# qr_reader.net
KiCad netlist of a schematic drawn in Altium Designer
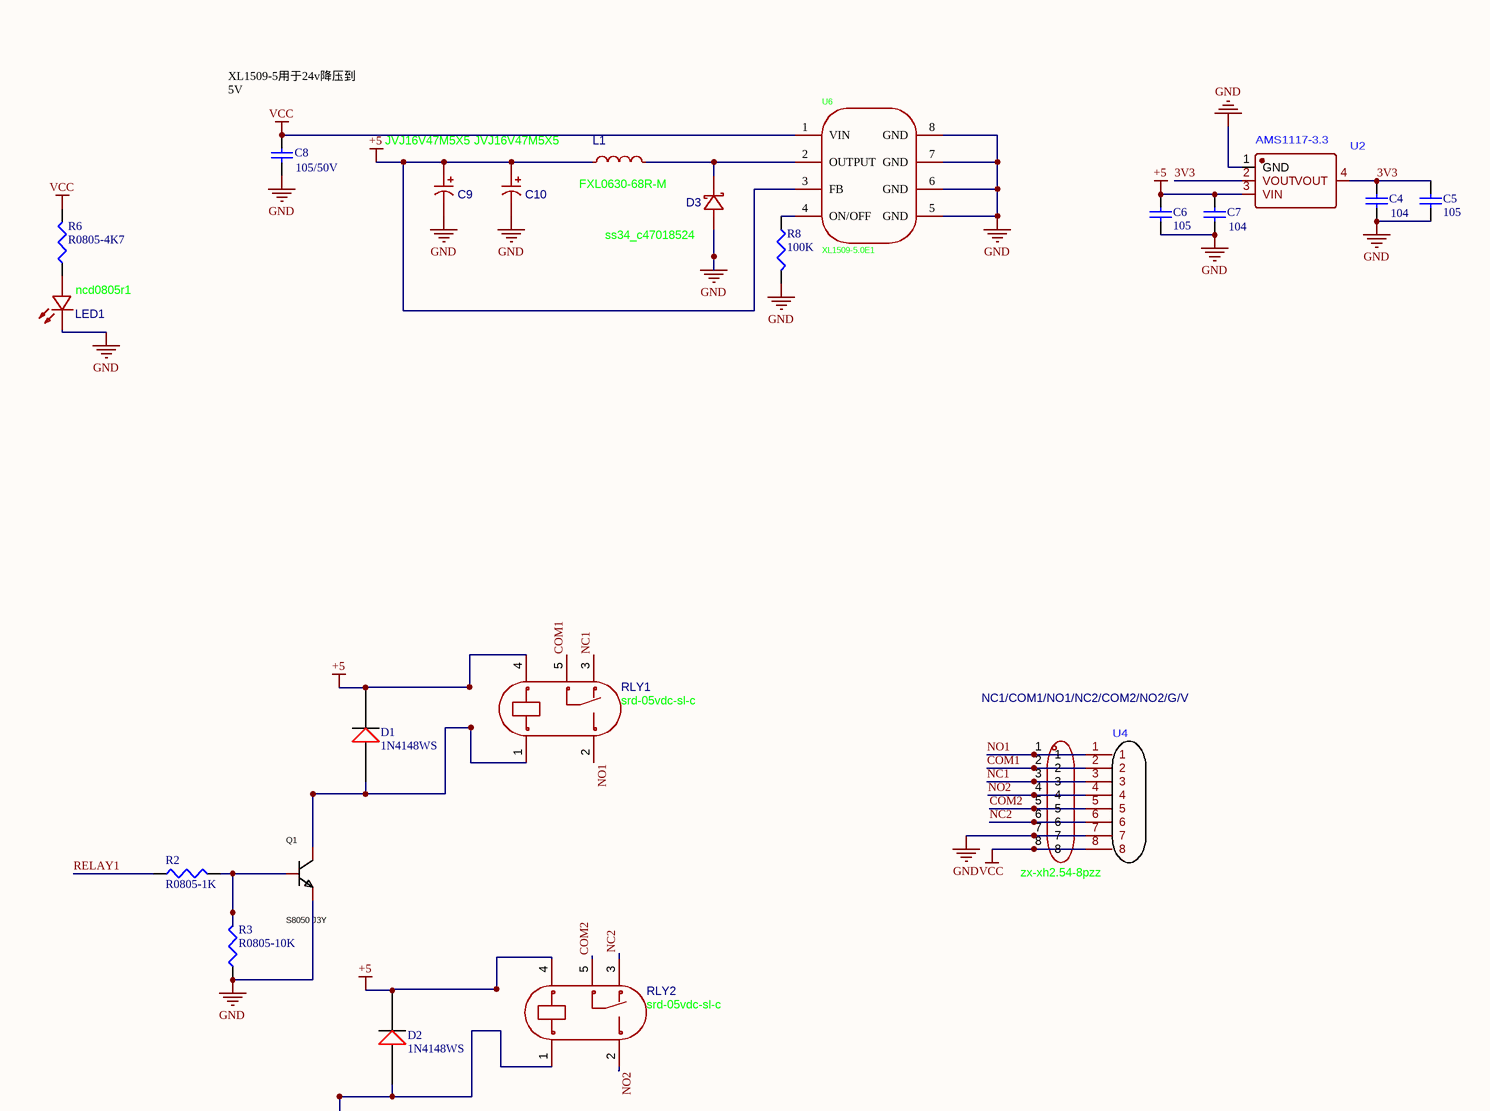
[diagram p0: qr reader.SchDoc, top left]
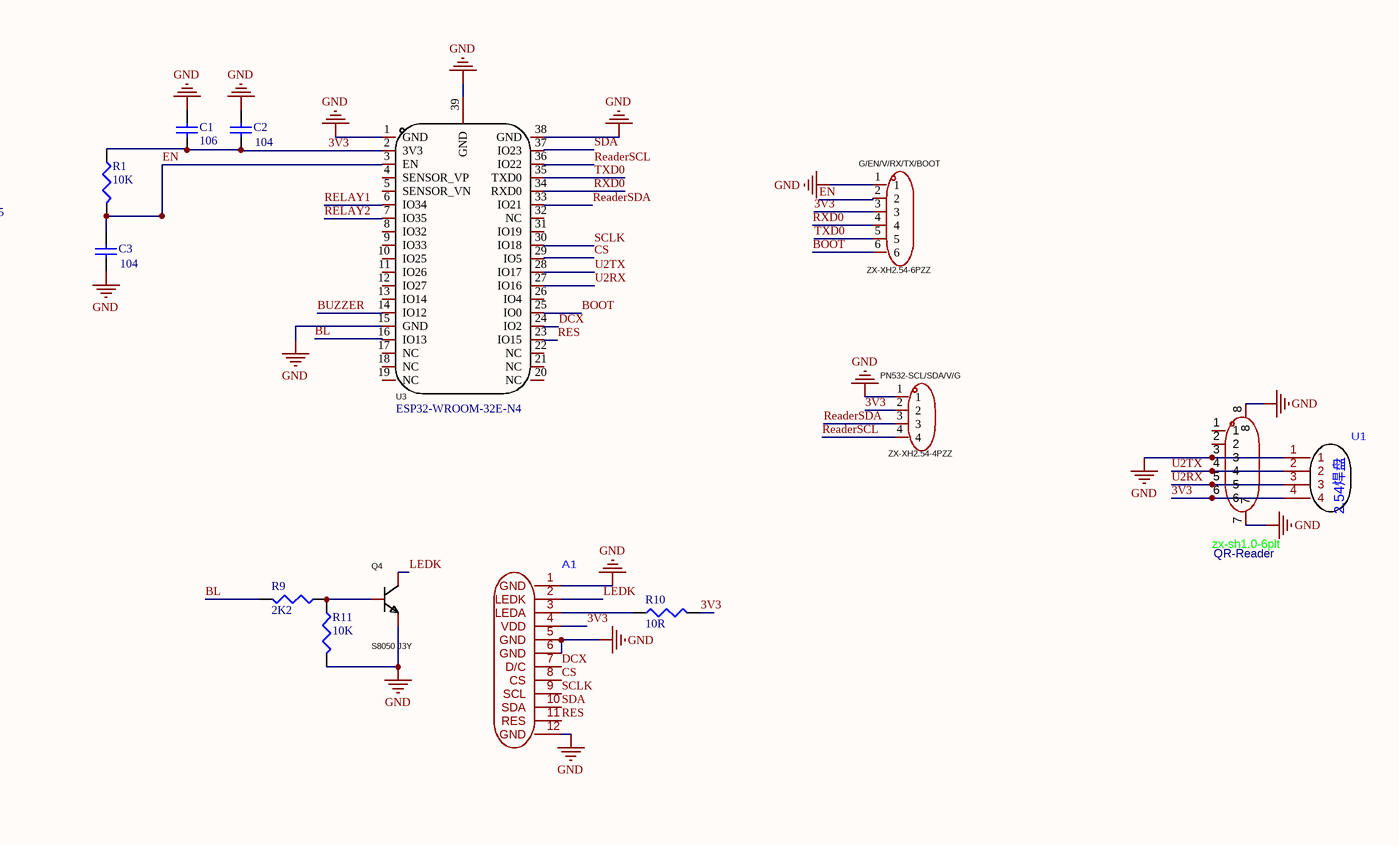
[diagram p1: qr reader.SchDoc, top right]
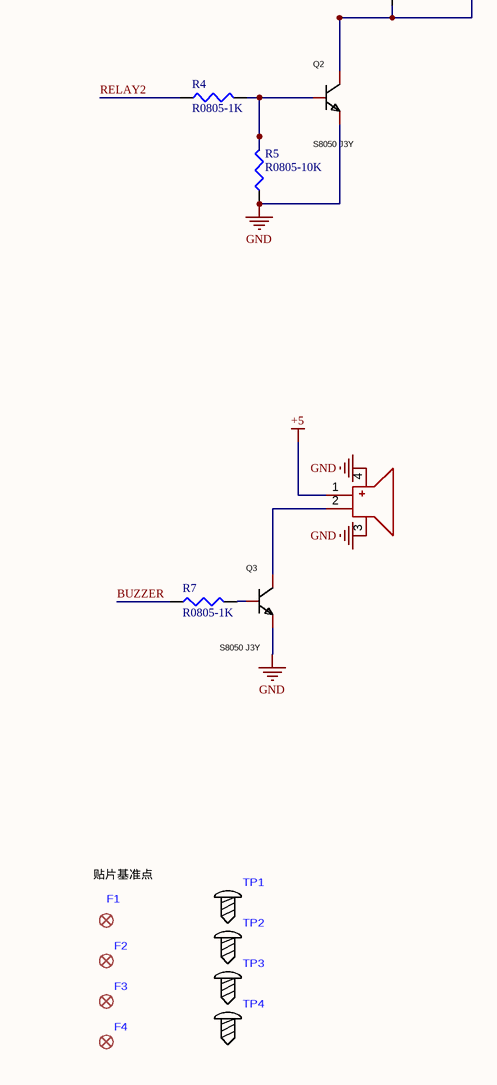
[diagram p2: qr reader.SchDoc, bottom left]

(export (version "E")
  (design (tool "Eeschema 10.0.6"))
  (components
    (comp (ref "A1")
      (value "~")
      (footprint "tft SCREEN")
      (libsource (lib "altium-import") (part "root_0_TFT1.54_"))
    )
    (comp (ref "BUZZER1")
      (value "klj-8530-5027")
      (footprint "BUZ-SMD_4P-L8.5-W8.5-TL")
      (fields (field (name "MANUFACTURER") "KELIKING(凯丽金)") (field (name "MANUFACTURERPART") "KLJ-8530-5027"))
      (libsource (lib "altium-import") (part "root_0_klj-8530-5027_"))
    )
    (comp (ref "C1")
      (value "106")
      (footprint "0805")
      (description "Capacitor (Semiconductor SIM Model)")
      (fields (field (name "Comment") "Cap Semi") (field (name "PUBLISHER") "Altium Limited"))
      (libsource (lib "Schlib1") (part "Cap Semi"))
    )
    (comp (ref "C2")
      (value "104")
      (footprint "0805")
      (description "Capacitor (Semiconductor SIM Model)")
      (fields (field (name "Comment") "Cap Semi") (field (name "PUBLISHER") "Altium Limited"))
      (libsource (lib "Schlib1") (part "Cap Semi"))
    )
    (comp (ref "C3")
      (value "104")
      (footprint "0805")
      (description "Capacitor (Semiconductor SIM Model)")
      (fields (field (name "Comment") "Cap Semi") (field (name "PUBLISHER") "Altium Limited"))
      (libsource (lib "Schlib1") (part "Cap Semi"))
    )
    (comp (ref "C4")
      (value "104")
      (footprint "0805")
      (description "Capacitor (Semiconductor SIM Model)")
      (fields (field (name "Comment") "Cap Semi") (field (name "PUBLISHER") "Altium Limited"))
      (libsource (lib "Schlib1") (part "Cap Semi"))
    )
    (comp (ref "C5")
      (value "105")
      (footprint "0805")
      (description "Capacitor (Semiconductor SIM Model)")
      (fields (field (name "Comment") "Cap Semi") (field (name "PUBLISHER") "Altium Limited"))
      (libsource (lib "Schlib1") (part "Cap Semi"))
    )
    (comp (ref "C6")
      (value "105")
      (footprint "0805")
      (description "Capacitor (Semiconductor SIM Model)")
      (fields (field (name "Comment") "Cap Semi") (field (name "PUBLISHER") "Altium Limited"))
      (libsource (lib "Schlib1") (part "Cap Semi"))
    )
    (comp (ref "C7")
      (value "104")
      (footprint "0805")
      (description "Capacitor (Semiconductor SIM Model)")
      (fields (field (name "Comment") "Cap Semi") (field (name "PUBLISHER") "Altium Limited"))
      (libsource (lib "Schlib1") (part "Cap Semi"))
    )
    (comp (ref "C8")
      (value "105/50V")
      (footprint "0805")
      (description "Capacitor (Semiconductor SIM Model)")
      (fields (field (name "Comment") "105") (field (name "PUBLISHER") "Altium Limited"))
      (libsource (lib "Schlib1") (part "Cap Semi"))
    )
    (comp (ref "C9")
      (value "JVJ16V47M5X5")
      (footprint "CAP-SMD_BD5.0-L5.3-W5.3-LS6.5-FD-1")
      (libsource (lib "altium-import") (part "root_3_JVJ16V47M5X5_"))
    )
    (comp (ref "C10")
      (value "JVJ16V47M5X5")
      (footprint "CAP-SMD_BD5.0-L5.3-W5.3-LS6.5-FD-1")
      (libsource (lib "altium-import") (part "root_3_JVJ16V47M5X5_"))
    )
    (comp (ref "D1") (value "1N4148WS") (footprint "SOD323") (libsource (lib "Schlib1") (part "1N4148WS")))
    (comp (ref "D2") (value "1N4148WS") (footprint "SOD323") (libsource (lib "Schlib1") (part "1N4148WS")))
    (comp (ref "D3")
      (value "ss34_c47018524")
      (footprint "SMA_L4.3-W2.6-LS5.0-RD")
      (description "二极管配置:独立式;直流反向耐压(Vr):40V;整流电流:3A;")
      (fields (field (name "MANUFACTURER") "baocheng(宝乘)") (field (name "MANUFACTURERPART") "SS34"))
      (libsource (lib "altium-import") (part "root_3_ss34_c47018524_"))
    )
    (comp (ref "F1")
      (value "~")
      (footprint "FIDUCIAL-1.5X3")
      (libsource (lib "altium-import") (part "root_0_FIDUCIAL1.5X3_"))
    )
    (comp (ref "F2")
      (value "~")
      (footprint "FIDUCIAL-1.5X3")
      (libsource (lib "altium-import") (part "root_0_FIDUCIAL1.5X3_"))
    )
    (comp (ref "F3")
      (value "~")
      (footprint "FIDUCIAL-1.5X3")
      (libsource (lib "altium-import") (part "root_0_FIDUCIAL1.5X3_"))
    )
    (comp (ref "F4")
      (value "~")
      (footprint "FIDUCIAL-1.5X3")
      (libsource (lib "altium-import") (part "root_0_FIDUCIAL1.5X3_"))
    )
    (comp (ref "G/EN/V/RX/TX/BOOT")
      (value "ZX-XH2.54-6PZZ")
      (footprint "CONN-TH_6P-P2.50_ZX-XH2.54-6PZZ")
      (fields (field (name "MANUFACTURER") "Megastar(兆星)"))
      (libsource (lib "altium-import") (part "root_0_ZX-XH2.54-6PZZ_"))
    )
    (comp (ref "L1")
      (value "FXL0630-68R-M")
      (footprint "0630 - duplicate")
      (libsource (lib "altium-import") (part "root_0_FXL0630-8R2-M_"))
    )
    (comp (ref "LED1")
      (value "ncd0805r1")
      (footprint "LED0805-RD")
      (fields (field (name "MANUFACTURER") "国星光电") (field (name "MANUFACTURERPART") "NCD0805R1"))
      (libsource (lib "altium-import") (part "root_1_ncd0805r1_"))
    )
    (comp (ref "NC1/COM1/NO1/NC2/COM2/NO2/G/V")
      (value "zx-xh2.54-8pzz")
      (footprint "CONN-TH_8P-P2.50-XH2.54-8P")
      (fields (field (name "MANUFACTURER") "Megastar(兆星)") (field (name "MANUFACTURERPART") "ZX-XH2.54-8PZZ"))
      (libsource (lib "altium-import") (part "root_0_zx-xh2.54-8pzz_"))
    )
    (comp (ref "PN532-SCL/SDA/V/G")
      (value "ZX-XH2.54-4PZZ")
      (footprint "CONN-TH_4P-P2.50_4PIN")
      (fields (field (name "MANUFACTURER") "Megastar(兆星)"))
      (libsource (lib "altium-import") (part "root_0_ZX-XH2.54-4PZZ_"))
    )
    (comp (ref "Q1")
      (value "S8050 J3Y")
      (footprint "SOT-23-3_L3.0-W1.7-P0.95-LS2.9-BR")
      (fields (field (name "MANUFACTURER") "CJ(江苏长电/长晶)"))
      (libsource (lib "altium-import") (part "root_0_S8050 J3Y_C2146_"))
    )
    (comp (ref "Q2")
      (value "S8050 J3Y")
      (footprint "SOT-23-3_L3.0-W1.7-P0.95-LS2.9-BR")
      (fields (field (name "MANUFACTURER") "CJ(江苏长电/长晶)"))
      (libsource (lib "altium-import") (part "root_0_S8050 J3Y_C2146_"))
    )
    (comp (ref "Q3")
      (value "S8050 J3Y")
      (footprint "SOT-23-3_L3.0-W1.7-P0.95-LS2.9-BR")
      (fields (field (name "MANUFACTURER") "CJ(江苏长电/长晶)"))
      (libsource (lib "altium-import") (part "root_0_S8050 J3Y_C2146_"))
    )
    (comp (ref "Q4")
      (value "S8050 J3Y")
      (footprint "SOT-23-3_L3.0-W1.7-P0.95-LS2.9-BR")
      (fields (field (name "MANUFACTURER") "CJ(江苏长电/长晶)"))
      (libsource (lib "altium-import") (part "root_0_S8050 J3Y_C2146_"))
    )
    (comp (ref "QR-Reader")
      (value "zx-sh1.0-6plt")
      (footprint "CONN-SMD_6P-P1.00_ZX-SH1.0-6PLT")
      (fields (field (name "MANUFACTURER") "Megastar(兆星)") (field (name "MANUFACTURERPART") "ZX-SH1.0-6PLT"))
      (libsource (lib "altium-import") (part "root_0_zx-sh1.0-6plt_"))
    )
    (comp (ref "R1")
      (value "10K")
      (footprint "0805")
      (description "Resistor")
      (fields (field (name "Comment") "Res3") (field (name "PUBLISHER") "Altium Limited"))
      (libsource (lib "Schlib1") (part "Res3"))
    )
    (comp (ref "R2")
      (value "R0805-1K")
      (footprint "0805")
      (description "Resistor")
      (fields (field (name "PUBLISHER") "Altium Limited"))
      (libsource (lib "Schlib1") (part "Res3"))
    )
    (comp (ref "R3")
      (value "R0805-10K")
      (footprint "0805")
      (description "Resistor")
      (fields (field (name "PUBLISHER") "Altium Limited"))
      (libsource (lib "Schlib1") (part "Res3"))
    )
    (comp (ref "R4")
      (value "R0805-1K")
      (footprint "0805")
      (description "Resistor")
      (fields (field (name "PUBLISHER") "Altium Limited"))
      (libsource (lib "Schlib1") (part "Res3"))
    )
    (comp (ref "R5")
      (value "R0805-10K")
      (footprint "0805")
      (description "Resistor")
      (fields (field (name "PUBLISHER") "Altium Limited"))
      (libsource (lib "Schlib1") (part "Res3"))
    )
    (comp (ref "R6")
      (value "R0805-4K7")
      (footprint "0805")
      (description "Resistor")
      (fields (field (name "PUBLISHER") "Altium Limited"))
      (libsource (lib "Schlib1") (part "Res3"))
    )
    (comp (ref "R7")
      (value "R0805-1K")
      (footprint "0805")
      (description "Resistor")
      (fields (field (name "PUBLISHER") "Altium Limited"))
      (libsource (lib "Schlib1") (part "Res3"))
    )
    (comp (ref "R8")
      (value "100K")
      (footprint "0805")
      (description "Resistor")
      (fields (field (name "PUBLISHER") "Altium Limited"))
      (libsource (lib "Schlib1") (part "Res3"))
    )
    (comp (ref "R9")
      (value "2K2")
      (footprint "0805")
      (description "Resistor")
      (fields (field (name "Comment") "Res3") (field (name "PUBLISHER") "Altium Limited"))
      (libsource (lib "Schlib1") (part "Res3"))
    )
    (comp (ref "R10")
      (value "10R")
      (footprint "0805")
      (description "Resistor")
      (fields (field (name "Comment") "Res3") (field (name "PUBLISHER") "Altium Limited"))
      (libsource (lib "Schlib1") (part "Res3"))
    )
    (comp (ref "R11")
      (value "10K")
      (footprint "0805")
      (description "Resistor")
      (fields (field (name "Comment") "Res3") (field (name "PUBLISHER") "Altium Limited"))
      (libsource (lib "Schlib1") (part "Res3"))
    )
    (comp (ref "RLY1")
      (value "srd-05vdc-sl-c")
      (footprint "RELAY-TH_SRD-XXVDC-XL-C")
      (description "线圈电压:5V;触点形式:一组转换:1C(单刀双掷-转换);触点容量(电阻负载):-;最大切换电压:250V@AC;最大切换电流:15A;")
      (fields (field (name "MANUFACTURER") "松乐") (field (name "MANUFACTURERPART") "SRD-05VDC-SL-C"))
      (libsource (lib "altium-import") (part "root_3_srd-05vdc-sl-c_"))
    )
    (comp (ref "RLY2")
      (value "srd-05vdc-sl-c")
      (footprint "RELAY-TH_SRD-XXVDC-XL-C")
      (description "线圈电压:5V;触点形式:一组转换:1C(单刀双掷-转换);触点容量(电阻负载):-;最大切换电压:250V@AC;最大切换电流:15A;")
      (fields (field (name "MANUFACTURER") "松乐") (field (name "MANUFACTURERPART") "SRD-05VDC-SL-C"))
      (libsource (lib "altium-import") (part "root_3_srd-05vdc-sl-c_"))
    )
    (comp (ref "TP1")
      (value "~")
      (footprint "PCBComponent_1 - duplicate")
      (libsource (lib "altium-import") (part "root_0_M3铜柱_"))
    )
    (comp (ref "TP2")
      (value "~")
      (footprint "PCBComponent_1 - duplicate")
      (libsource (lib "altium-import") (part "root_0_M3铜柱_"))
    )
    (comp (ref "TP3")
      (value "~")
      (footprint "PCBComponent_1 - duplicate")
      (libsource (lib "altium-import") (part "root_0_M3铜柱_"))
    )
    (comp (ref "TP4")
      (value "~")
      (footprint "PCBComponent_1 - duplicate")
      (libsource (lib "altium-import") (part "root_0_M3铜柱_"))
    )
    (comp (ref "U1")
      (value "~")
      (footprint "2.54_PAD_4P")
      (libsource (lib "altium-import") (part "root_0_当面2.54焊盘_"))
    )
    (comp (ref "U2")
      (value "AMS1117-3.3")
      (footprint "SOT-223-3_L6.7-W3.7-P2.30-LS7.0-BR")
      (libsource (lib "altium-import") (part "root_0_AMS1117-3.3_C917183_"))
    )
    (comp (ref "U3")
      (value "ESP32-WROOM-32E-N4")
      (footprint "WIFI-SMD_ESP32-WROOM-32E")
      (fields (field (name "MANUFACTURER") "ESPRESSIF(乐鑫)"))
      (libsource (lib "altium-import") (part "root_0_ESP32-WROOM-32E-N4_"))
    )
    (comp (ref "U4")
      (value "~")
      (footprint "3.96_PAD_8P")
      (libsource (lib "altium-import") (part "root_2_8P焊盘底面层_"))
    )
    (comp (ref "U6")
      (value "XL1509-5.0E1")
      (footprint "SOIC-8_L5.0-W4.0-P1.27-LS6.0-BL")
      (fields (field (name "MANUFACTURER") "XLSEMI(芯龙)"))
      (libsource (lib "altium-import") (part "root_0_XL1509-5.0E1_"))
    )
  )
  (nets
    (net (code "1") (name "+5") (class "Default")
      (node (ref "BUZZER1") (pin "1") (pinfunction "+_1") (pintype "passive"))
      (node (ref "C10") (pin "1") (pinfunction "1_1") (pintype "passive"))
      (node (ref "C6") (pin "1") (pinfunction "1_1") (pintype "passive"))
      (node (ref "C7") (pin "2") (pinfunction "2_2") (pintype "passive"))
      (node (ref "C9") (pin "1") (pinfunction "1_1") (pintype "passive"))
      (node (ref "D1") (pin "2") (pinfunction "2_2") (pintype "passive"))
      (node (ref "D2") (pin "2") (pinfunction "2_2") (pintype "passive"))
      (node (ref "L1") (pin "1") (pinfunction "1_1") (pintype "passive"))
      (node (ref "RLY1") (pin "4") (pinfunction "4_4") (pintype "passive"))
      (node (ref "RLY2") (pin "4") (pinfunction "4_4") (pintype "passive"))
      (node (ref "U2") (pin "3") (pinfunction "VIN_3") (pintype "passive"))
      (node (ref "U6") (pin "3") (pinfunction "FB_3") (pintype "passive"))
    )
    (net (code "2") (name "/3V3") (class "Default")
      (node (ref "A1") (pin "4") (pinfunction "VDD_4") (pintype "passive"))
      (node (ref "C1") (pin "2") (pinfunction "2_2") (pintype "passive"))
      (node (ref "C2") (pin "1") (pinfunction "1_1") (pintype "passive"))
      (node (ref "C4") (pin "2") (pinfunction "2_2") (pintype "passive"))
      (node (ref "C5") (pin "1") (pinfunction "1_1") (pintype "passive"))
      (node (ref "G/EN/V/RX/TX/BOOT") (pin "3") (pinfunction "3_3") (pintype "passive"))
      (node (ref "PN532-SCL/SDA/V/G") (pin "2") (pinfunction "2_2") (pintype "passive"))
      (node (ref "QR-Reader") (pin "6") (pinfunction "6_6") (pintype "passive"))
      (node (ref "R1") (pin "1") (pinfunction "1_1") (pintype "passive"))
      (node (ref "R10") (pin "2") (pinfunction "2_2") (pintype "passive"))
      (node (ref "U1") (pin "4") (pinfunction "4_4") (pintype "passive"))
      (node (ref "U2") (pin "2") (pinfunction "VOUT_2") (pintype "passive"))
      (node (ref "U2") (pin "4") (pinfunction "VOUT_4") (pintype "passive"))
      (node (ref "U3") (pin "2") (pinfunction "3V3_2") (pintype "passive"))
    )
    (net (code "3") (name "/BL") (class "Default")
      (node (ref "R9") (pin "2") (pinfunction "2_2") (pintype "passive"))
      (node (ref "U3") (pin "16") (pinfunction "IO13_16") (pintype "passive"))
    )
    (net (code "4") (name "/BOOT") (class "Default")
      (node (ref "G/EN/V/RX/TX/BOOT") (pin "6") (pinfunction "6_6") (pintype "passive"))
      (node (ref "U3") (pin "25") (pinfunction "IO0_25") (pintype "passive"))
    )
    (net (code "5") (name "/BUZZER") (class "Default")
      (node (ref "R7") (pin "1") (pinfunction "1_1") (pintype "passive"))
      (node (ref "U3") (pin "14") (pinfunction "IO12_14") (pintype "passive"))
    )
    (net (code "6") (name "/COM1") (class "Default")
      (node (ref "NC1/COM1/NO1/NC2/COM2/NO2/G/V") (pin "2") (pinfunction "2_2") (pintype "passive"))
      (node (ref "RLY1") (pin "5") (pinfunction "5_5") (pintype "passive"))
      (node (ref "U4") (pin "2") (pinfunction "2_2") (pintype "passive"))
    )
    (net (code "7") (name "/COM2") (class "Default")
      (node (ref "NC1/COM1/NO1/NC2/COM2/NO2/G/V") (pin "5") (pinfunction "5_5") (pintype "passive"))
      (node (ref "RLY2") (pin "5") (pinfunction "5_5") (pintype "passive"))
      (node (ref "U4") (pin "5") (pinfunction "5_5") (pintype "passive"))
    )
    (net (code "8") (name "/CS") (class "Default")
      (node (ref "A1") (pin "8") (pinfunction "CS_8") (pintype "passive"))
      (node (ref "U3") (pin "29") (pinfunction "IO5_29") (pintype "passive"))
    )
    (net (code "9") (name "/DCX") (class "Default")
      (node (ref "A1") (pin "7") (pinfunction "D/C_7") (pintype "passive"))
      (node (ref "U3") (pin "24") (pinfunction "IO2_24") (pintype "passive"))
    )
    (net (code "10") (name "/EN") (class "Default")
      (node (ref "C3") (pin "2") (pinfunction "2_2") (pintype "passive"))
      (node (ref "G/EN/V/RX/TX/BOOT") (pin "2") (pinfunction "2_2") (pintype "passive"))
      (node (ref "R1") (pin "2") (pinfunction "2_2") (pintype "passive"))
      (node (ref "U3") (pin "3") (pinfunction "EN_3") (pintype "passive"))
    )
    (net (code "11") (name "/LEDK") (class "Default")
      (node (ref "A1") (pin "2") (pinfunction "LEDK_2") (pintype "passive"))
      (node (ref "Q4") (pin "3") (pinfunction "C_3") (pintype "passive"))
    )
    (net (code "12") (name "/NC1") (class "Default")
      (node (ref "NC1/COM1/NO1/NC2/COM2/NO2/G/V") (pin "3") (pinfunction "3_3") (pintype "passive"))
      (node (ref "RLY1") (pin "3") (pinfunction "3_3") (pintype "passive"))
      (node (ref "U4") (pin "3") (pinfunction "3_3") (pintype "passive"))
    )
    (net (code "13") (name "/NC2") (class "Default")
      (node (ref "NC1/COM1/NO1/NC2/COM2/NO2/G/V") (pin "6") (pinfunction "6_6") (pintype "passive"))
      (node (ref "RLY2") (pin "3") (pinfunction "3_3") (pintype "passive"))
      (node (ref "U4") (pin "6") (pinfunction "6_6") (pintype "passive"))
    )
    (net (code "14") (name "/NO1") (class "Default")
      (node (ref "NC1/COM1/NO1/NC2/COM2/NO2/G/V") (pin "1") (pinfunction "1_1") (pintype "passive"))
      (node (ref "RLY1") (pin "2") (pinfunction "2_2") (pintype "passive"))
      (node (ref "U4") (pin "1") (pinfunction "1_1") (pintype "passive"))
    )
    (net (code "15") (name "/NO2") (class "Default")
      (node (ref "NC1/COM1/NO1/NC2/COM2/NO2/G/V") (pin "4") (pinfunction "4_4") (pintype "passive"))
      (node (ref "RLY2") (pin "2") (pinfunction "2_2") (pintype "passive"))
      (node (ref "U4") (pin "4") (pinfunction "4_4") (pintype "passive"))
    )
    (net (code "16") (name "/RELAY1") (class "Default")
      (node (ref "R2") (pin "1") (pinfunction "1_1") (pintype "passive"))
      (node (ref "U3") (pin "6") (pinfunction "IO34_6") (pintype "passive"))
    )
    (net (code "17") (name "/RELAY2") (class "Default")
      (node (ref "R4") (pin "1") (pinfunction "1_1") (pintype "passive"))
      (node (ref "U3") (pin "7") (pinfunction "IO35_7") (pintype "passive"))
    )
    (net (code "18") (name "/RES") (class "Default")
      (node (ref "A1") (pin "11") (pinfunction "RES_11") (pintype "passive"))
      (node (ref "U3") (pin "23") (pinfunction "IO15_23") (pintype "passive"))
    )
    (net (code "19") (name "/RXD0") (class "Default")
      (node (ref "G/EN/V/RX/TX/BOOT") (pin "4") (pinfunction "4_4") (pintype "passive"))
      (node (ref "U3") (pin "34") (pinfunction "RXD0_34") (pintype "passive"))
    )
    (net (code "20") (name "/ReaderSCL") (class "Default")
      (node (ref "PN532-SCL/SDA/V/G") (pin "4") (pinfunction "4_4") (pintype "passive"))
      (node (ref "U3") (pin "36") (pinfunction "IO22_36") (pintype "passive"))
    )
    (net (code "21") (name "/ReaderSDA") (class "Default")
      (node (ref "PN532-SCL/SDA/V/G") (pin "3") (pinfunction "3_3") (pintype "passive"))
      (node (ref "U3") (pin "33") (pinfunction "IO21_33") (pintype "passive"))
    )
    (net (code "22") (name "/SCLK") (class "Default")
      (node (ref "A1") (pin "9") (pinfunction "SCL_9") (pintype "passive"))
      (node (ref "U3") (pin "30") (pinfunction "IO18_30") (pintype "passive"))
    )
    (net (code "23") (name "/SDA") (class "Default")
      (node (ref "A1") (pin "10") (pinfunction "SDA_10") (pintype "passive"))
      (node (ref "U3") (pin "37") (pinfunction "IO23_37") (pintype "passive"))
    )
    (net (code "24") (name "/TXD0") (class "Default")
      (node (ref "G/EN/V/RX/TX/BOOT") (pin "5") (pinfunction "5_5") (pintype "passive"))
      (node (ref "U3") (pin "35") (pinfunction "TXD0_35") (pintype "passive"))
    )
    (net (code "25") (name "/U2RX") (class "Default")
      (node (ref "QR-Reader") (pin "5") (pinfunction "5_5") (pintype "passive"))
      (node (ref "U1") (pin "3") (pinfunction "3_3") (pintype "passive"))
      (node (ref "U3") (pin "27") (pinfunction "IO16_27") (pintype "passive"))
    )
    (net (code "26") (name "/U2TX") (class "Default")
      (node (ref "QR-Reader") (pin "4") (pinfunction "4_4") (pintype "passive"))
      (node (ref "U1") (pin "2") (pinfunction "2_2") (pintype "passive"))
      (node (ref "U3") (pin "28") (pinfunction "IO17_28") (pintype "passive"))
    )
    (net (code "27") (name "GND") (class "Default")
      (node (ref "A1") (pin "1") (pinfunction "GND_1") (pintype "passive"))
      (node (ref "A1") (pin "12") (pinfunction "GND_12") (pintype "passive"))
      (node (ref "A1") (pin "5") (pinfunction "GND_5") (pintype "passive"))
      (node (ref "A1") (pin "6") (pinfunction "GND_6") (pintype "passive"))
      (node (ref "BUZZER1") (pin "3") (pinfunction "NC_3") (pintype "passive"))
      (node (ref "BUZZER1") (pin "4") (pinfunction "NC_4") (pintype "passive"))
      (node (ref "C1") (pin "1") (pinfunction "1_1") (pintype "passive"))
      (node (ref "C10") (pin "2") (pinfunction "2_2") (pintype "passive"))
      (node (ref "C2") (pin "2") (pinfunction "2_2") (pintype "passive"))
      (node (ref "C3") (pin "1") (pinfunction "1_1") (pintype "passive"))
      (node (ref "C4") (pin "1") (pinfunction "1_1") (pintype "passive"))
      (node (ref "C5") (pin "2") (pinfunction "2_2") (pintype "passive"))
      (node (ref "C6") (pin "2") (pinfunction "2_2") (pintype "passive"))
      (node (ref "C7") (pin "1") (pinfunction "1_1") (pintype "passive"))
      (node (ref "C8") (pin "1") (pinfunction "1_1") (pintype "passive"))
      (node (ref "C9") (pin "2") (pinfunction "2_2") (pintype "passive"))
      (node (ref "D3") (pin "2") (pinfunction "A_2") (pintype "passive"))
      (node (ref "G/EN/V/RX/TX/BOOT") (pin "1") (pinfunction "1_1") (pintype "passive"))
      (node (ref "LED1") (pin "1") (pinfunction "-_1") (pintype "passive"))
      (node (ref "NC1/COM1/NO1/NC2/COM2/NO2/G/V") (pin "7") (pinfunction "7_7") (pintype "passive"))
      (node (ref "PN532-SCL/SDA/V/G") (pin "1") (pinfunction "1_1") (pintype "passive"))
      (node (ref "Q1") (pin "2") (pinfunction "E_2") (pintype "passive"))
      (node (ref "Q2") (pin "2") (pinfunction "E_2") (pintype "passive"))
      (node (ref "Q3") (pin "2") (pinfunction "E_2") (pintype "passive"))
      (node (ref "Q4") (pin "2") (pinfunction "E_2") (pintype "passive"))
      (node (ref "QR-Reader") (pin "3") (pinfunction "3_3") (pintype "passive"))
      (node (ref "QR-Reader") (pin "7") (pinfunction "7_7") (pintype "passive"))
      (node (ref "QR-Reader") (pin "8") (pinfunction "8_8") (pintype "passive"))
      (node (ref "R11") (pin "2") (pinfunction "2_2") (pintype "passive"))
      (node (ref "R3") (pin "1") (pinfunction "1_1") (pintype "passive"))
      (node (ref "R5") (pin "1") (pinfunction "1_1") (pintype "passive"))
      (node (ref "R8") (pin "2") (pinfunction "2_2") (pintype "passive"))
      (node (ref "U1") (pin "1") (pinfunction "1_1") (pintype "passive"))
      (node (ref "U2") (pin "1") (pinfunction "GND_1") (pintype "passive"))
      (node (ref "U3") (pin "1") (pinfunction "GND_1") (pintype "passive"))
      (node (ref "U3") (pin "15") (pinfunction "GND_15") (pintype "passive"))
      (node (ref "U3") (pin "38") (pinfunction "GND_38") (pintype "passive"))
      (node (ref "U3") (pin "39") (pinfunction "GND_39") (pintype "passive"))
      (node (ref "U4") (pin "7") (pinfunction "7_7") (pintype "passive"))
      (node (ref "U6") (pin "5") (pinfunction "GND_5") (pintype "passive"))
      (node (ref "U6") (pin "6") (pinfunction "GND_6") (pintype "passive"))
      (node (ref "U6") (pin "7") (pinfunction "GND_7") (pintype "passive"))
      (node (ref "U6") (pin "8") (pinfunction "GND_8") (pintype "passive"))
    )
    (net (code "28") (name "Net-(A1-LEDA)") (class "Default")
      (node (ref "A1") (pin "3") (pinfunction "LEDA_3") (pintype "passive"))
      (node (ref "R10") (pin "1") (pinfunction "1_1") (pintype "passive"))
    )
    (net (code "29") (name "Net-(BUZZER1--)") (class "Default")
      (node (ref "BUZZER1") (pin "2") (pinfunction "-_2") (pintype "passive"))
      (node (ref "Q3") (pin "3") (pinfunction "C_3") (pintype "passive"))
    )
    (net (code "30") (name "Net-(D3-C)") (class "Default")
      (node (ref "D3") (pin "1") (pinfunction "C_1") (pintype "passive"))
      (node (ref "L1") (pin "2") (pinfunction "2_2") (pintype "passive"))
      (node (ref "U6") (pin "2") (pinfunction "OUTPUT_2") (pintype "passive"))
    )
    (net (code "31") (name "Net-(LED1-+)") (class "Default")
      (node (ref "LED1") (pin "2") (pinfunction "+_2") (pintype "passive"))
      (node (ref "R6") (pin "1") (pinfunction "1_1") (pintype "passive"))
    )
    (net (code "32") (name "Net-(Q1-B)") (class "Default")
      (node (ref "Q1") (pin "1") (pinfunction "B_1") (pintype "passive"))
      (node (ref "R2") (pin "2") (pinfunction "2_2") (pintype "passive"))
      (node (ref "R3") (pin "2") (pinfunction "2_2") (pintype "passive"))
    )
    (net (code "33") (name "Net-(Q1-C)") (class "Default")
      (node (ref "D1") (pin "1") (pinfunction "1_1") (pintype "passive"))
      (node (ref "Q1") (pin "3") (pinfunction "C_3") (pintype "passive"))
      (node (ref "RLY1") (pin "1") (pinfunction "1_1") (pintype "passive"))
    )
    (net (code "34") (name "Net-(Q2-B)") (class "Default")
      (node (ref "Q2") (pin "1") (pinfunction "B_1") (pintype "passive"))
      (node (ref "R4") (pin "2") (pinfunction "2_2") (pintype "passive"))
      (node (ref "R5") (pin "2") (pinfunction "2_2") (pintype "passive"))
    )
    (net (code "35") (name "Net-(Q2-C)") (class "Default")
      (node (ref "D2") (pin "1") (pinfunction "1_1") (pintype "passive"))
      (node (ref "Q2") (pin "3") (pinfunction "C_3") (pintype "passive"))
      (node (ref "RLY2") (pin "1") (pinfunction "1_1") (pintype "passive"))
    )
    (net (code "36") (name "Net-(Q3-B)") (class "Default")
      (node (ref "Q3") (pin "1") (pinfunction "B_1") (pintype "passive"))
      (node (ref "R7") (pin "2") (pinfunction "2_2") (pintype "passive"))
    )
    (net (code "37") (name "Net-(Q4-B)") (class "Default")
      (node (ref "Q4") (pin "1") (pinfunction "B_1") (pintype "passive"))
      (node (ref "R11") (pin "1") (pinfunction "1_1") (pintype "passive"))
      (node (ref "R9") (pin "1") (pinfunction "1_1") (pintype "passive"))
    )
    (net (code "38") (name "Net-(U6-ON{slash}OFF)") (class "Default")
      (node (ref "R8") (pin "1") (pinfunction "1_1") (pintype "passive"))
      (node (ref "U6") (pin "4") (pinfunction "ON/OFF_4") (pintype "passive"))
    )
    (net (code "39") (name "VCC") (class "Default")
      (node (ref "C8") (pin "2") (pinfunction "2_2") (pintype "passive"))
      (node (ref "NC1/COM1/NO1/NC2/COM2/NO2/G/V") (pin "8") (pinfunction "8_8") (pintype "passive"))
      (node (ref "R6") (pin "2") (pinfunction "2_2") (pintype "passive"))
      (node (ref "U4") (pin "8") (pinfunction "8_8") (pintype "passive"))
      (node (ref "U6") (pin "1") (pinfunction "VIN_1") (pintype "passive"))
    )
    (net (code "40") (name "unconnected-(QR-Reader-Pad1)") (class "Default")
      (node (ref "QR-Reader") (pin "1") (pinfunction "1_1") (pintype "passive"))
    )
    (net (code "41") (name "unconnected-(QR-Reader-Pad2)") (class "Default")
      (node (ref "QR-Reader") (pin "2") (pinfunction "2_2") (pintype "passive"))
    )
    (net (code "42") (name "unconnected-(U3-IO4-Pad26)") (class "Default")
      (node (ref "U3") (pin "26") (pinfunction "IO4_26") (pintype "passive"))
    )
    (net (code "43") (name "unconnected-(U3-IO14-Pad13)") (class "Default")
      (node (ref "U3") (pin "13") (pinfunction "IO14_13") (pintype "passive"))
    )
    (net (code "44") (name "unconnected-(U3-IO19-Pad31)") (class "Default")
      (node (ref "U3") (pin "31") (pinfunction "IO19_31") (pintype "passive"))
    )
    (net (code "45") (name "unconnected-(U3-IO25-Pad10)") (class "Default")
      (node (ref "U3") (pin "10") (pinfunction "IO25_10") (pintype "passive"))
    )
    (net (code "46") (name "unconnected-(U3-IO26-Pad11)") (class "Default")
      (node (ref "U3") (pin "11") (pinfunction "IO26_11") (pintype "passive"))
    )
    (net (code "47") (name "unconnected-(U3-IO27-Pad12)") (class "Default")
      (node (ref "U3") (pin "12") (pinfunction "IO27_12") (pintype "passive"))
    )
    (net (code "48") (name "unconnected-(U3-IO32-Pad8)") (class "Default")
      (node (ref "U3") (pin "8") (pinfunction "IO32_8") (pintype "passive"))
    )
    (net (code "49") (name "unconnected-(U3-IO33-Pad9)") (class "Default")
      (node (ref "U3") (pin "9") (pinfunction "IO33_9") (pintype "passive"))
    )
    (net (code "50") (name "unconnected-(U3-NC-Pad17)") (class "Default")
      (node (ref "U3") (pin "17") (pinfunction "NC_17") (pintype "passive"))
    )
    (net (code "51") (name "unconnected-(U3-NC-Pad18)") (class "Default")
      (node (ref "U3") (pin "18") (pinfunction "NC_18") (pintype "passive"))
    )
    (net (code "52") (name "unconnected-(U3-NC-Pad19)") (class "Default")
      (node (ref "U3") (pin "19") (pinfunction "NC_19") (pintype "passive"))
    )
    (net (code "53") (name "unconnected-(U3-NC-Pad20)") (class "Default")
      (node (ref "U3") (pin "20") (pinfunction "NC_20") (pintype "passive"))
    )
    (net (code "54") (name "unconnected-(U3-NC-Pad21)") (class "Default")
      (node (ref "U3") (pin "21") (pinfunction "NC_21") (pintype "passive"))
    )
    (net (code "55") (name "unconnected-(U3-NC-Pad22)") (class "Default")
      (node (ref "U3") (pin "22") (pinfunction "NC_22") (pintype "passive"))
    )
    (net (code "56") (name "unconnected-(U3-NC-Pad32)") (class "Default")
      (node (ref "U3") (pin "32") (pinfunction "NC_32") (pintype "passive"))
    )
    (net (code "57") (name "unconnected-(U3-SENSOR_VN-Pad5)") (class "Default")
      (node (ref "U3") (pin "5") (pinfunction "SENSOR_VN_5") (pintype "passive"))
    )
    (net (code "58") (name "unconnected-(U3-SENSOR_VP-Pad4)") (class "Default")
      (node (ref "U3") (pin "4") (pinfunction "SENSOR_VP_4") (pintype "passive"))
    )
  )
)
